# proc.net
KiCad netlist of a schematic drawn in EAGLE
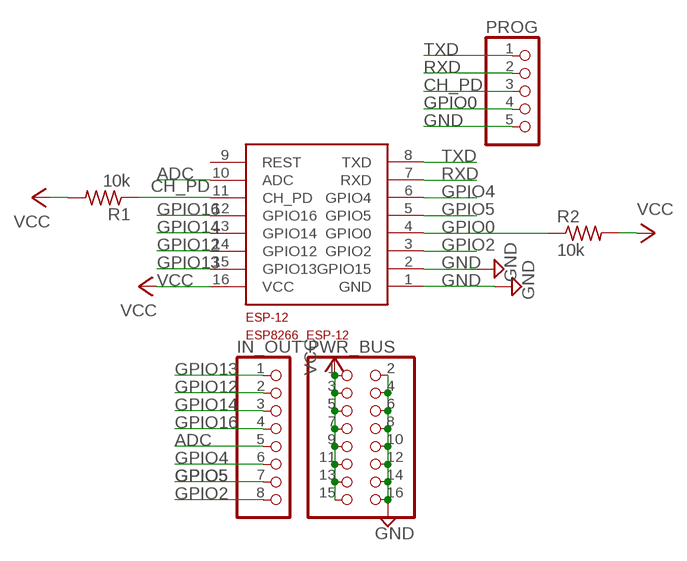
[diagram p0: schematic, sheet 1]

(export (version "E")
  (design (tool "Eeschema 10.0.6"))
  (components
    (comp (ref "ESP-12")
      (value "ESP8266_ESP-12")
      (footprint "eagle-import:ESP8266-ESP12")
      (libsource (lib "eagle-import") (part "ESP8266_ESP-12"))
    )
    (comp (ref "IN_OUT")
      (value "PINHD-1X8")
      (footprint "eagle-import:1X08")
      (libsource (lib "eagle-import") (part "PINHD-1X8"))
    )
    (comp (ref "PROG")
      (value "PINHD-1X5")
      (footprint "eagle-import:1X05")
      (libsource (lib "eagle-import") (part "PINHD-1X5"))
    )
    (comp (ref "PWR_BUS")
      (value "PINHD-2X8")
      (footprint "eagle-import:2X08")
      (libsource (lib "eagle-import") (part "PINHD-2X8"))
    )
    (comp (ref "R1")
      (value "10k")
      (footprint "eagle-import:M1206")
      (libsource (lib "eagle-import") (part "R-US_M1206"))
    )
    (comp (ref "R2")
      (value "10k")
      (footprint "eagle-import:M1206")
      (libsource (lib "eagle-import") (part "R-US_M1206"))
    )
  )
  (nets
    (net (code "1") (name "/ADC") (class "Default")
      (node (ref "ESP-12") (pin "10") (pinfunction "ADC_10") (pintype "bidirectional"))
      (node (ref "IN_OUT") (pin "5") (pinfunction "5_5") (pintype "passive"))
    )
    (net (code "2") (name "/CH_PD") (class "Default")
      (node (ref "ESP-12") (pin "11") (pinfunction "CH_PD_11") (pintype "bidirectional"))
      (node (ref "PROG") (pin "3") (pinfunction "3_3") (pintype "passive"))
      (node (ref "R1") (pin "1") (pinfunction "1_1") (pintype "passive"))
    )
    (net (code "3") (name "/GPIO0") (class "Default")
      (node (ref "ESP-12") (pin "4") (pinfunction "GPIO0_4") (pintype "bidirectional"))
      (node (ref "PROG") (pin "4") (pinfunction "4_4") (pintype "passive"))
      (node (ref "R2") (pin "1") (pinfunction "1_1") (pintype "passive"))
    )
    (net (code "4") (name "/GPIO2") (class "Default")
      (node (ref "ESP-12") (pin "3") (pinfunction "GPIO2_3") (pintype "bidirectional"))
      (node (ref "IN_OUT") (pin "8") (pinfunction "8_8") (pintype "passive"))
    )
    (net (code "5") (name "/GPIO4") (class "Default")
      (node (ref "ESP-12") (pin "6") (pinfunction "GPIO4_6") (pintype "bidirectional"))
      (node (ref "IN_OUT") (pin "6") (pinfunction "6_6") (pintype "passive"))
    )
    (net (code "6") (name "/GPIO5") (class "Default")
      (node (ref "ESP-12") (pin "5") (pinfunction "GPIO5_5") (pintype "bidirectional"))
      (node (ref "IN_OUT") (pin "7") (pinfunction "7_7") (pintype "passive"))
    )
    (net (code "7") (name "/GPIO12") (class "Default")
      (node (ref "ESP-12") (pin "14") (pinfunction "GPIO12_14") (pintype "bidirectional"))
      (node (ref "IN_OUT") (pin "2") (pinfunction "2_2") (pintype "passive"))
    )
    (net (code "8") (name "/GPIO13") (class "Default")
      (node (ref "ESP-12") (pin "15") (pinfunction "GPIO13_15") (pintype "bidirectional"))
      (node (ref "IN_OUT") (pin "1") (pinfunction "1_1") (pintype "passive"))
    )
    (net (code "9") (name "/GPIO14") (class "Default")
      (node (ref "ESP-12") (pin "13") (pinfunction "GPIO14_13") (pintype "bidirectional"))
      (node (ref "IN_OUT") (pin "3") (pinfunction "3_3") (pintype "passive"))
    )
    (net (code "10") (name "/GPIO16") (class "Default")
      (node (ref "ESP-12") (pin "12") (pinfunction "GPIO16_12") (pintype "bidirectional"))
      (node (ref "IN_OUT") (pin "4") (pinfunction "4_4") (pintype "passive"))
    )
    (net (code "11") (name "/RXD") (class "Default")
      (node (ref "ESP-12") (pin "7") (pinfunction "RXD_7") (pintype "bidirectional"))
      (node (ref "PROG") (pin "2") (pinfunction "2_2") (pintype "passive"))
    )
    (net (code "12") (name "/TXD") (class "Default")
      (node (ref "ESP-12") (pin "8") (pinfunction "TXD_8") (pintype "bidirectional"))
      (node (ref "PROG") (pin "1") (pinfunction "1_1") (pintype "passive"))
    )
    (net (code "13") (name "GND") (class "Default")
      (node (ref "ESP-12") (pin "1") (pinfunction "GND_1") (pintype "bidirectional"))
      (node (ref "ESP-12") (pin "2") (pinfunction "GPIO15_2") (pintype "bidirectional"))
      (node (ref "PROG") (pin "5") (pinfunction "5_5") (pintype "passive"))
      (node (ref "PWR_BUS") (pin "10") (pinfunction "10_10") (pintype "passive"))
      (node (ref "PWR_BUS") (pin "12") (pinfunction "12_12") (pintype "passive"))
      (node (ref "PWR_BUS") (pin "14") (pinfunction "14_14") (pintype "passive"))
      (node (ref "PWR_BUS") (pin "16") (pinfunction "16_16") (pintype "passive"))
      (node (ref "PWR_BUS") (pin "2") (pinfunction "2_2") (pintype "passive"))
      (node (ref "PWR_BUS") (pin "4") (pinfunction "4_4") (pintype "passive"))
      (node (ref "PWR_BUS") (pin "6") (pinfunction "6_6") (pintype "passive"))
      (node (ref "PWR_BUS") (pin "8") (pinfunction "8_8") (pintype "passive"))
    )
    (net (code "14") (name "VCC") (class "Default")
      (node (ref "ESP-12") (pin "16") (pinfunction "VCC_16") (pintype "bidirectional"))
      (node (ref "PWR_BUS") (pin "1") (pinfunction "1_1") (pintype "passive"))
      (node (ref "PWR_BUS") (pin "11") (pinfunction "11_11") (pintype "passive"))
      (node (ref "PWR_BUS") (pin "13") (pinfunction "13_13") (pintype "passive"))
      (node (ref "PWR_BUS") (pin "15") (pinfunction "15_15") (pintype "passive"))
      (node (ref "PWR_BUS") (pin "3") (pinfunction "3_3") (pintype "passive"))
      (node (ref "PWR_BUS") (pin "5") (pinfunction "5_5") (pintype "passive"))
      (node (ref "PWR_BUS") (pin "7") (pinfunction "7_7") (pintype "passive"))
      (node (ref "PWR_BUS") (pin "9") (pinfunction "9_9") (pintype "passive"))
      (node (ref "R1") (pin "2") (pinfunction "2_2") (pintype "passive"))
      (node (ref "R2") (pin "2") (pinfunction "2_2") (pintype "passive"))
    )
    (net (code "15") (name "unconnected-(ESP-12-REST-Pad9)") (class "Default")
      (node (ref "ESP-12") (pin "9") (pinfunction "REST_9") (pintype "bidirectional"))
    )
  )
)
